# DD2090_4CAM_FFC_EEPROM.net
KiCad netlist of a schematic drawn in Altium Designer
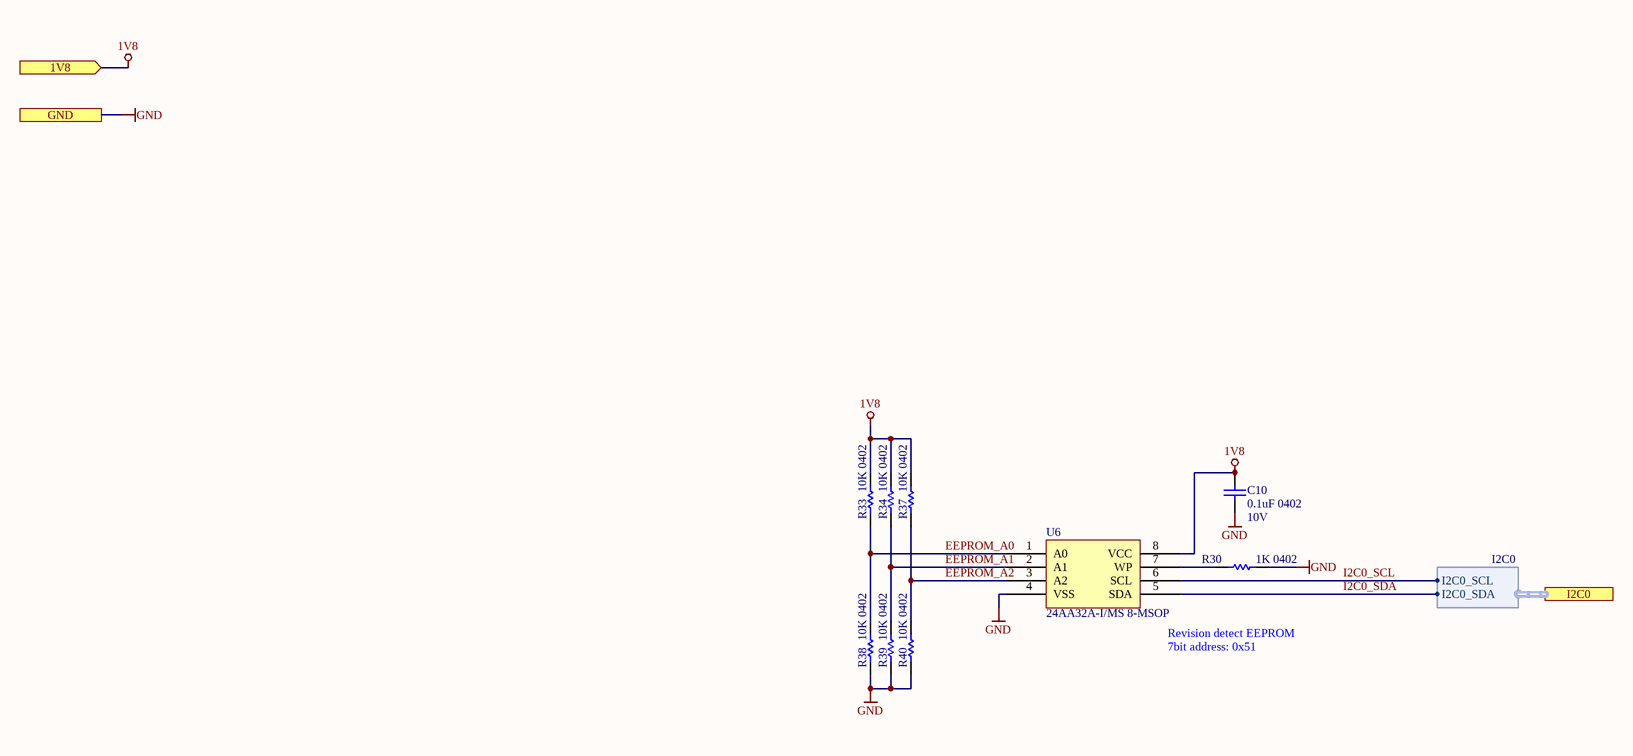
[diagram p0: DD2090_4CAM_FFC_EEPROM.SchDoc]

(export (version "E")
  (design (tool "Eeschema 10.0.6"))
  (components
    (comp (ref "C10")
      (value "0.1uF 0402")
      (footprint "CAP_Altium_Vault_Generic:CAPC0402(1005)70_L")
      (description "CAP CER 0.1UF 10V X7R 0402 5%")
      (fields (field (name "TOLERANCE") "5%") (field (name "VOLTAGE RATING") "10V"))
      (libsource (lib "LuxonisMaster") (part "GRM155R71A104JA01D"))
    )
    (comp (ref "R30")
      (value "1K 0402")
      (footprint "RES_Altium_Vault_Generic:RESC0402(1005)_L")
      (description "RES SMD 1K OHM 1% 1/16W 0402")
      (fields (field (name "TOLERANCE") "1%"))
      (libsource (lib "LuxonisMaster") (part "RC0402FR-071KL"))
    )
    (comp (ref "R33")
      (value "10K 0402")
      (footprint "RES_Altium_Vault_Generic:RESC0402(1005)_L")
      (fields (field (name "TOLERANCE") "1%"))
      (libsource (lib "LuxonisMaster") (part "RC0402FR-1310KL"))
    )
    (comp (ref "R34")
      (value "10K 0402")
      (footprint "RES_Altium_Vault_Generic:RESC0402(1005)_L")
      (fields (field (name "TOLERANCE") "1%"))
      (libsource (lib "LuxonisMaster") (part "RC0402FR-1310KL"))
    )
    (comp (ref "R37")
      (value "10K 0402")
      (footprint "RES_Altium_Vault_Generic:RESC0402(1005)_L")
      (fields (field (name "TOLERANCE") "1%"))
      (libsource (lib "LuxonisMaster") (part "RC0402FR-1310KL"))
    )
    (comp (ref "R38")
      (value "10K 0402")
      (footprint "RES_Altium_Vault_Generic:RESC0402(1005)_L")
      (fields (field (name "TOLERANCE") "1%"))
      (libsource (lib "LuxonisMaster") (part "RC0402FR-1310KL"))
    )
    (comp (ref "R39")
      (value "10K 0402")
      (footprint "RES_Altium_Vault_Generic:RESC0402(1005)_L")
      (fields (field (name "TOLERANCE") "1%"))
      (libsource (lib "LuxonisMaster") (part "RC0402FR-1310KL"))
    )
    (comp (ref "R40")
      (value "10K 0402")
      (footprint "RES_Altium_Vault_Generic:RESC0402(1005)_L")
      (fields (field (name "TOLERANCE") "1%"))
      (libsource (lib "LuxonisMaster") (part "RC0402FR-1310KL"))
    )
    (comp (ref "U6")
      (value "24AA32A-I/MS 8-MSOP")
      (footprint "LuxonisMaster:24AA32A-I/MS")
      (description "IC EEPROM 32K I2C 400KHZ 8MSOP Memory IC 32Kb (4K x 8) I²C 400kHz 900ns 8-MSOP")
      (libsource (lib "LuxonisMaster") (part "24AA32A-I/MS"))
    )
  )
  (nets
    (net (code "2") (name "/EEPROM_A0") (class "Default")
      (node (ref "R33") (pin "1") (pinfunction "1_1") (pintype "passive"))
      (node (ref "R38") (pin "2") (pinfunction "2_2") (pintype "passive"))
      (node (ref "U6") (pin "1") (pinfunction "A0_1") (pintype "passive"))
    )
    (net (code "3") (name "/EEPROM_A1") (class "Default")
      (node (ref "R34") (pin "1") (pinfunction "1_1") (pintype "passive"))
      (node (ref "R39") (pin "2") (pinfunction "2_2") (pintype "passive"))
      (node (ref "U6") (pin "2") (pinfunction "A1_2") (pintype "passive"))
    )
    (net (code "4") (name "/EEPROM_A2") (class "Default")
      (node (ref "R37") (pin "1") (pinfunction "1_1") (pintype "passive"))
      (node (ref "R40") (pin "2") (pinfunction "2_2") (pintype "passive"))
      (node (ref "U6") (pin "3") (pinfunction "A2_3") (pintype "passive"))
    )
    (net (code "5") (name "/I2C0_SCL") (class "Default")
      (node (ref "U6") (pin "6") (pinfunction "SCL_6") (pintype "passive"))
    )
    (net (code "6") (name "/I2C0_SDA") (class "Default")
      (node (ref "U6") (pin "5") (pinfunction "SDA_5") (pintype "passive"))
    )
    (net (code "8") (name "1V8") (class "Default")
      (node (ref "C10") (pin "2") (pinfunction "2_2") (pintype "passive"))
      (node (ref "R33") (pin "2") (pinfunction "2_2") (pintype "passive"))
      (node (ref "R34") (pin "2") (pinfunction "2_2") (pintype "passive"))
      (node (ref "R37") (pin "2") (pinfunction "2_2") (pintype "passive"))
      (node (ref "U6") (pin "8") (pinfunction "VCC_8") (pintype "passive"))
    )
    (net (code "9") (name "GND") (class "Default")
      (node (ref "C10") (pin "1") (pinfunction "1_1") (pintype "passive"))
      (node (ref "R30") (pin "1") (pinfunction "1_1") (pintype "passive"))
      (node (ref "R38") (pin "1") (pinfunction "1_1") (pintype "passive"))
      (node (ref "R39") (pin "1") (pinfunction "1_1") (pintype "passive"))
      (node (ref "R40") (pin "1") (pinfunction "1_1") (pintype "passive"))
      (node (ref "U6") (pin "4") (pinfunction "VSS_4") (pintype "passive"))
    )
    (net (code "10") (name "Net-(U6-WP)") (class "Default")
      (node (ref "R30") (pin "2") (pinfunction "2_2") (pintype "passive"))
      (node (ref "U6") (pin "7") (pinfunction "WP_7") (pintype "passive"))
    )
  )
)
